# power.net
KiCad netlist of a schematic drawn in Altium Designer
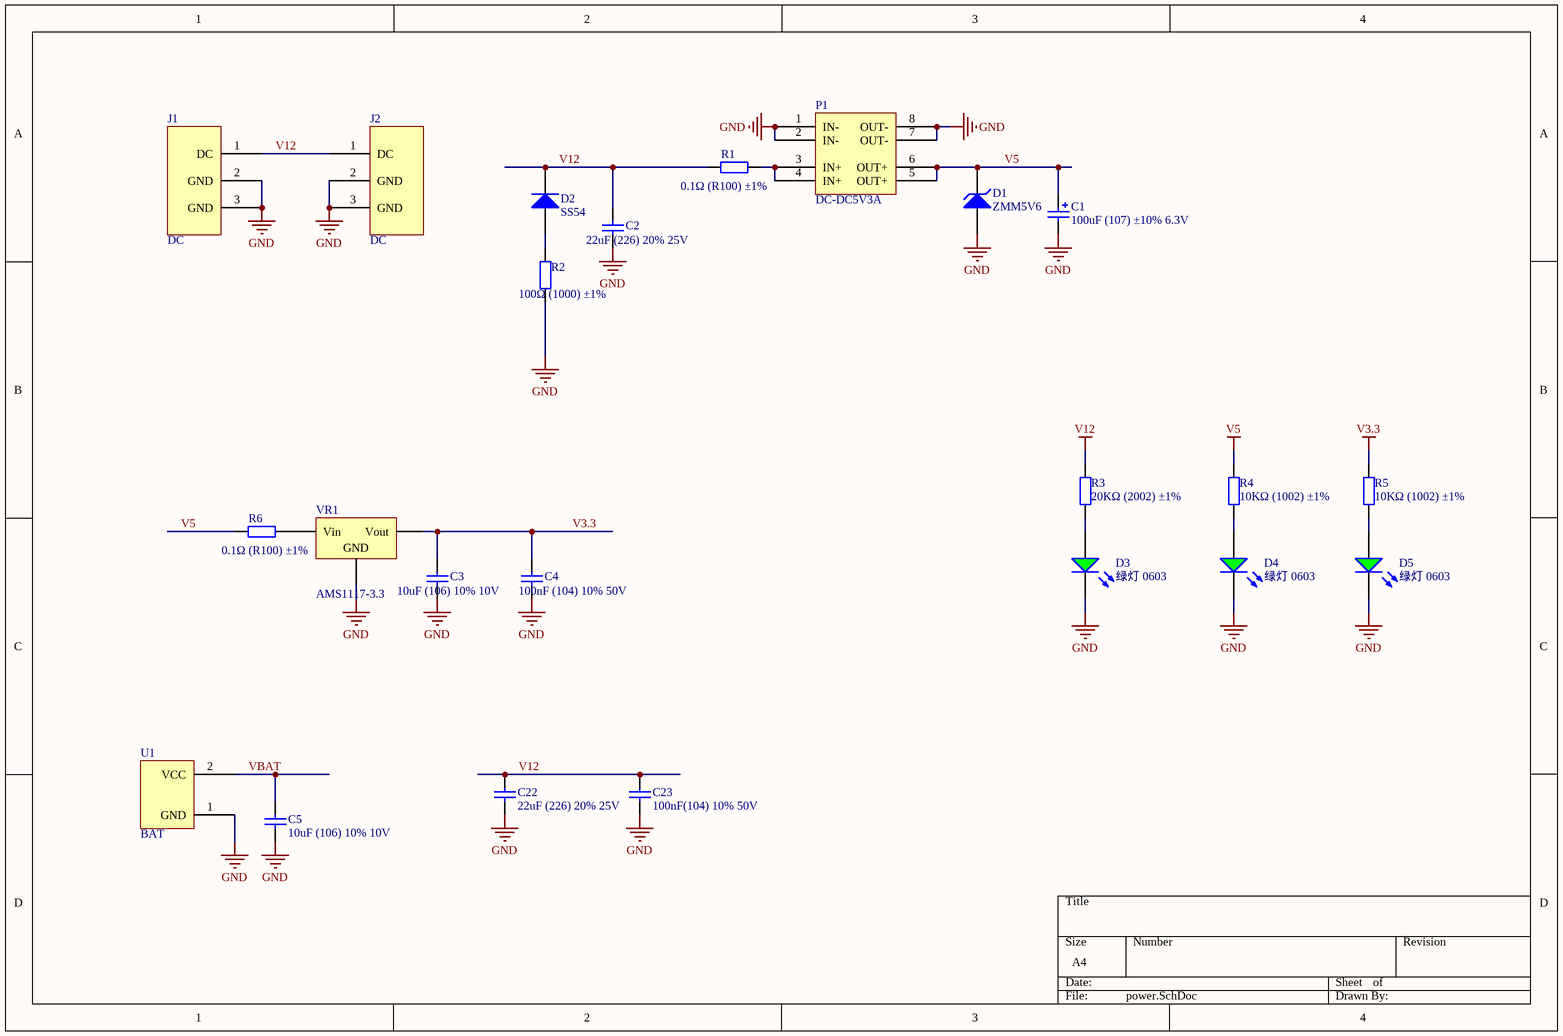
[diagram p0: power.SchDoc]

(export (version "E")
  (design (tool "Eeschema 10.0.6"))
  (components
    (comp (ref "C1")
      (value "100uF (107) ±10% 6.3V")
      (footprint "CASE-B_3528")
      (description "钽电容")
      (libsource (lib "Miscellaneous Devices LC") (part "3528 100uF (107) 10% 6.3V"))
    )
    (comp (ref "C2")
      (value "22uF (226) 20% 25V")
      (footprint "0805_C")
      (description "贴片电容")
      (libsource (lib "Miscellaneous Devices LC") (part "0805 22uF (226) 20% 25V"))
    )
    (comp (ref "C3")
      (value "10uF (106) 10% 10V")
      (footprint "0603_C")
      (description "贴片电容")
      (libsource (lib "Miscellaneous Devices LC") (part "0603 10uF (106) 10% 10V"))
    )
    (comp (ref "C4")
      (value "100nF (104) 10% 50V")
      (footprint "0603_C")
      (description "贴片电容")
      (libsource (lib "Miscellaneous Devices LC") (part "0603 100nF (104) 10% 50V"))
    )
    (comp (ref "C5")
      (value "10uF (106) 10% 10V")
      (footprint "0603_C")
      (description "贴片电容")
      (libsource (lib "Miscellaneous Devices LC") (part "0603 10uF (106) 10% 10V"))
    )
    (comp (ref "C22")
      (value "22uF (226) 20% 25V")
      (footprint "0805_C")
      (description "贴片电容")
      (libsource (lib "Miscellaneous Devices LC") (part "0805 22uF (226) 20% 25V"))
    )
    (comp (ref "C23")
      (value "100nF(104) 10% 50V")
      (footprint "0805_C")
      (description "贴片电容")
      (libsource (lib "Miscellaneous Devices LC") (part "0805 100nF(104) 10% 50V"))
    )
    (comp (ref "D1")
      (value "ZMM5V6")
      (footprint "LL-34")
      (description "稳压二极管")
      (libsource (lib "Miscellaneous Devices LC") (part "LL-34 ZMM5V6"))
    )
    (comp (ref "D2")
      (value "SS54")
      (footprint "SMA(DO-214AC)_S1")
      (description "二极管")
      (libsource (lib "Miscellaneous Devices LC") (part "SMA(DO-214AC) SS54"))
    )
    (comp (ref "D3")
      (value "绿灯 0603")
      (footprint "0603_LED_S1")
      (description "发光二极管")
      (libsource (lib "Miscellaneous Devices LC") (part "0603 绿灯"))
    )
    (comp (ref "D4")
      (value "绿灯 0603")
      (footprint "0603_LED_S1")
      (description "发光二极管")
      (libsource (lib "Miscellaneous Devices LC") (part "0603 绿灯"))
    )
    (comp (ref "D5")
      (value "绿灯 0603")
      (footprint "0603_LED_S1")
      (description "发光二极管")
      (libsource (lib "Miscellaneous Devices LC") (part "0603 绿灯"))
    )
    (comp (ref "J1")
      (value "DC")
      (footprint "DC005")
      (description "Connector for DC 12V")
      (libsource (lib "CHK-I") (part "DC"))
    )
    (comp (ref "J2")
      (value "DC")
      (footprint "DC005")
      (description "Connector for DC 12V")
      (libsource (lib "") (part "DC_1"))
    )
    (comp (ref "P1") (value "DC-DC5V3A") (footprint "DC-DC3A") (libsource (lib "CHK-I") (part "DC-DC3A")))
    (comp (ref "R1")
      (value "0.1Ω (R100) ±1%")
      (footprint "1206_R")
      (description "贴片电阻")
      (libsource (lib "Miscellaneous Devices LC") (part "1206 0.1Ω (R100) 1%"))
    )
    (comp (ref "R2")
      (value "100Ω (1000) ±1%")
      (footprint "0805_R")
      (description "贴片电阻")
      (libsource (lib "Miscellaneous Devices LC") (part "0805 100Ω (1000) 1%"))
    )
    (comp (ref "R3")
      (value "20KΩ (2002) ±1%")
      (footprint "0603_R")
      (description "贴片电阻")
      (libsource (lib "Miscellaneous Devices LC") (part "0603 20KΩ (2002) 1%"))
    )
    (comp (ref "R4")
      (value "10KΩ (1002) ±1%")
      (footprint "0603_R")
      (description "贴片电阻")
      (libsource (lib "Miscellaneous Devices LC") (part "0603 10KΩ (1002) 1%"))
    )
    (comp (ref "R5")
      (value "10KΩ (1002) ±1%")
      (footprint "0603_R")
      (description "贴片电阻")
      (libsource (lib "Miscellaneous Devices LC") (part "0603 10KΩ (1002) 1%"))
    )
    (comp (ref "R6")
      (value "0.1Ω (R100) ±1%")
      (footprint "1206_R")
      (description "贴片电阻")
      (libsource (lib "Miscellaneous Devices LC") (part "1206 0.1Ω (R100) 1%"))
    )
    (comp (ref "U1") (value "BAT") (footprint "BAT2032") (libsource (lib "CHK-I") (part "BAT2032")))
    (comp (ref "VR1")
      (value "AMS1117-3.3")
      (footprint "SOT-223")
      (description "低压差线性稳压(LDO)")
      (libsource (lib "Miscellaneous Devices LC") (part "SOT-223 AMS1117-3.3"))
    )
  )
  (nets
    (net (code "1") (name "/VBAT") (class "Default")
      (node (ref "C5") (pin "2") (pinfunction "2_2") (pintype "passive"))
      (node (ref "U1") (pin "2") (pinfunction "VCC_2") (pintype "passive"))
    )
    (net (code "2") (name "GND") (class "Default")
      (node (ref "C1") (pin "2") (pinfunction "2_2") (pintype "passive"))
      (node (ref "C2") (pin "1") (pinfunction "1_1") (pintype "passive"))
      (node (ref "C22") (pin "1") (pinfunction "1_1") (pintype "passive"))
      (node (ref "C23") (pin "1") (pinfunction "1_1") (pintype "passive"))
      (node (ref "C3") (pin "1") (pinfunction "1_1") (pintype "passive"))
      (node (ref "C4") (pin "1") (pinfunction "1_1") (pintype "passive"))
      (node (ref "C5") (pin "1") (pinfunction "1_1") (pintype "passive"))
      (node (ref "D1") (pin "1") (pinfunction "A_1") (pintype "passive"))
      (node (ref "D3") (pin "K") (pinfunction "K_K") (pintype "passive"))
      (node (ref "D4") (pin "K") (pinfunction "K_K") (pintype "passive"))
      (node (ref "D5") (pin "K") (pinfunction "K_K") (pintype "passive"))
      (node (ref "J1") (pin "2") (pinfunction "GND_2") (pintype "passive"))
      (node (ref "J1") (pin "3") (pinfunction "GND_3") (pintype "passive"))
      (node (ref "J2") (pin "2") (pinfunction "GND_2") (pintype "passive"))
      (node (ref "J2") (pin "3") (pinfunction "GND_3") (pintype "passive"))
      (node (ref "P1") (pin "1") (pinfunction "IN-_1") (pintype "passive"))
      (node (ref "P1") (pin "2") (pinfunction "IN-_2") (pintype "passive"))
      (node (ref "P1") (pin "7") (pinfunction "OUT-_7") (pintype "passive"))
      (node (ref "P1") (pin "8") (pinfunction "OUT-_8") (pintype "passive"))
      (node (ref "R2") (pin "1") (pinfunction "1_1") (pintype "passive"))
      (node (ref "U1") (pin "1") (pinfunction "GND_1") (pintype "passive"))
      (node (ref "VR1") (pin "1") (pinfunction "GND_1") (pintype "passive"))
    )
    (net (code "3") (name "Net-(D2-A)") (class "Default")
      (node (ref "D2") (pin "1") (pinfunction "A_1") (pintype "passive"))
      (node (ref "R2") (pin "2") (pinfunction "2_2") (pintype "passive"))
    )
    (net (code "4") (name "Net-(D3-PadA)") (class "Default")
      (node (ref "D3") (pin "A") (pinfunction "A_A") (pintype "passive"))
      (node (ref "R3") (pin "1") (pinfunction "1_1") (pintype "passive"))
    )
    (net (code "5") (name "Net-(D4-PadA)") (class "Default")
      (node (ref "D4") (pin "A") (pinfunction "A_A") (pintype "passive"))
      (node (ref "R4") (pin "1") (pinfunction "1_1") (pintype "passive"))
    )
    (net (code "6") (name "Net-(D5-PadA)") (class "Default")
      (node (ref "D5") (pin "A") (pinfunction "A_A") (pintype "passive"))
      (node (ref "R5") (pin "1") (pinfunction "1_1") (pintype "passive"))
    )
    (net (code "7") (name "Net-(P1-IN+-Pad3)") (class "Default")
      (node (ref "P1") (pin "3") (pinfunction "IN+_3") (pintype "passive"))
      (node (ref "P1") (pin "4") (pinfunction "IN+_4") (pintype "passive"))
      (node (ref "R1") (pin "2") (pinfunction "2_2") (pintype "passive"))
    )
    (net (code "8") (name "Net-(VR1-Vin)") (class "Default")
      (node (ref "R6") (pin "2") (pinfunction "2_2") (pintype "passive"))
      (node (ref "VR1") (pin "3") (pinfunction "Vin_3") (pintype "passive"))
    )
    (net (code "9") (name "V3.3") (class "Default")
      (node (ref "C3") (pin "2") (pinfunction "2_2") (pintype "passive"))
      (node (ref "C4") (pin "2") (pinfunction "2_2") (pintype "passive"))
      (node (ref "R5") (pin "2") (pinfunction "2_2") (pintype "passive"))
      (node (ref "VR1") (pin "2") (pinfunction "Vout_2") (pintype "passive"))
    )
    (net (code "10") (name "V5") (class "Default")
      (node (ref "C1") (pin "1") (pinfunction "1_1") (pintype "passive"))
      (node (ref "D1") (pin "2") (pinfunction "K_2") (pintype "passive"))
      (node (ref "P1") (pin "5") (pinfunction "OUT+_5") (pintype "passive"))
      (node (ref "P1") (pin "6") (pinfunction "OUT+_6") (pintype "passive"))
      (node (ref "R4") (pin "2") (pinfunction "2_2") (pintype "passive"))
      (node (ref "R6") (pin "1") (pinfunction "1_1") (pintype "passive"))
    )
    (net (code "11") (name "V12") (class "Default")
      (node (ref "C2") (pin "2") (pinfunction "2_2") (pintype "passive"))
      (node (ref "C22") (pin "2") (pinfunction "2_2") (pintype "passive"))
      (node (ref "C23") (pin "2") (pinfunction "2_2") (pintype "passive"))
      (node (ref "D2") (pin "2") (pinfunction "K_2") (pintype "passive"))
      (node (ref "J1") (pin "1") (pinfunction "DC_1") (pintype "passive"))
      (node (ref "J2") (pin "1") (pinfunction "DC_1") (pintype "passive"))
      (node (ref "R1") (pin "1") (pinfunction "1_1") (pintype "passive"))
      (node (ref "R3") (pin "2") (pinfunction "2_2") (pintype "passive"))
    )
  )
)
